# Peripherals.net
KiCad netlist of a schematic drawn in Altium Designer
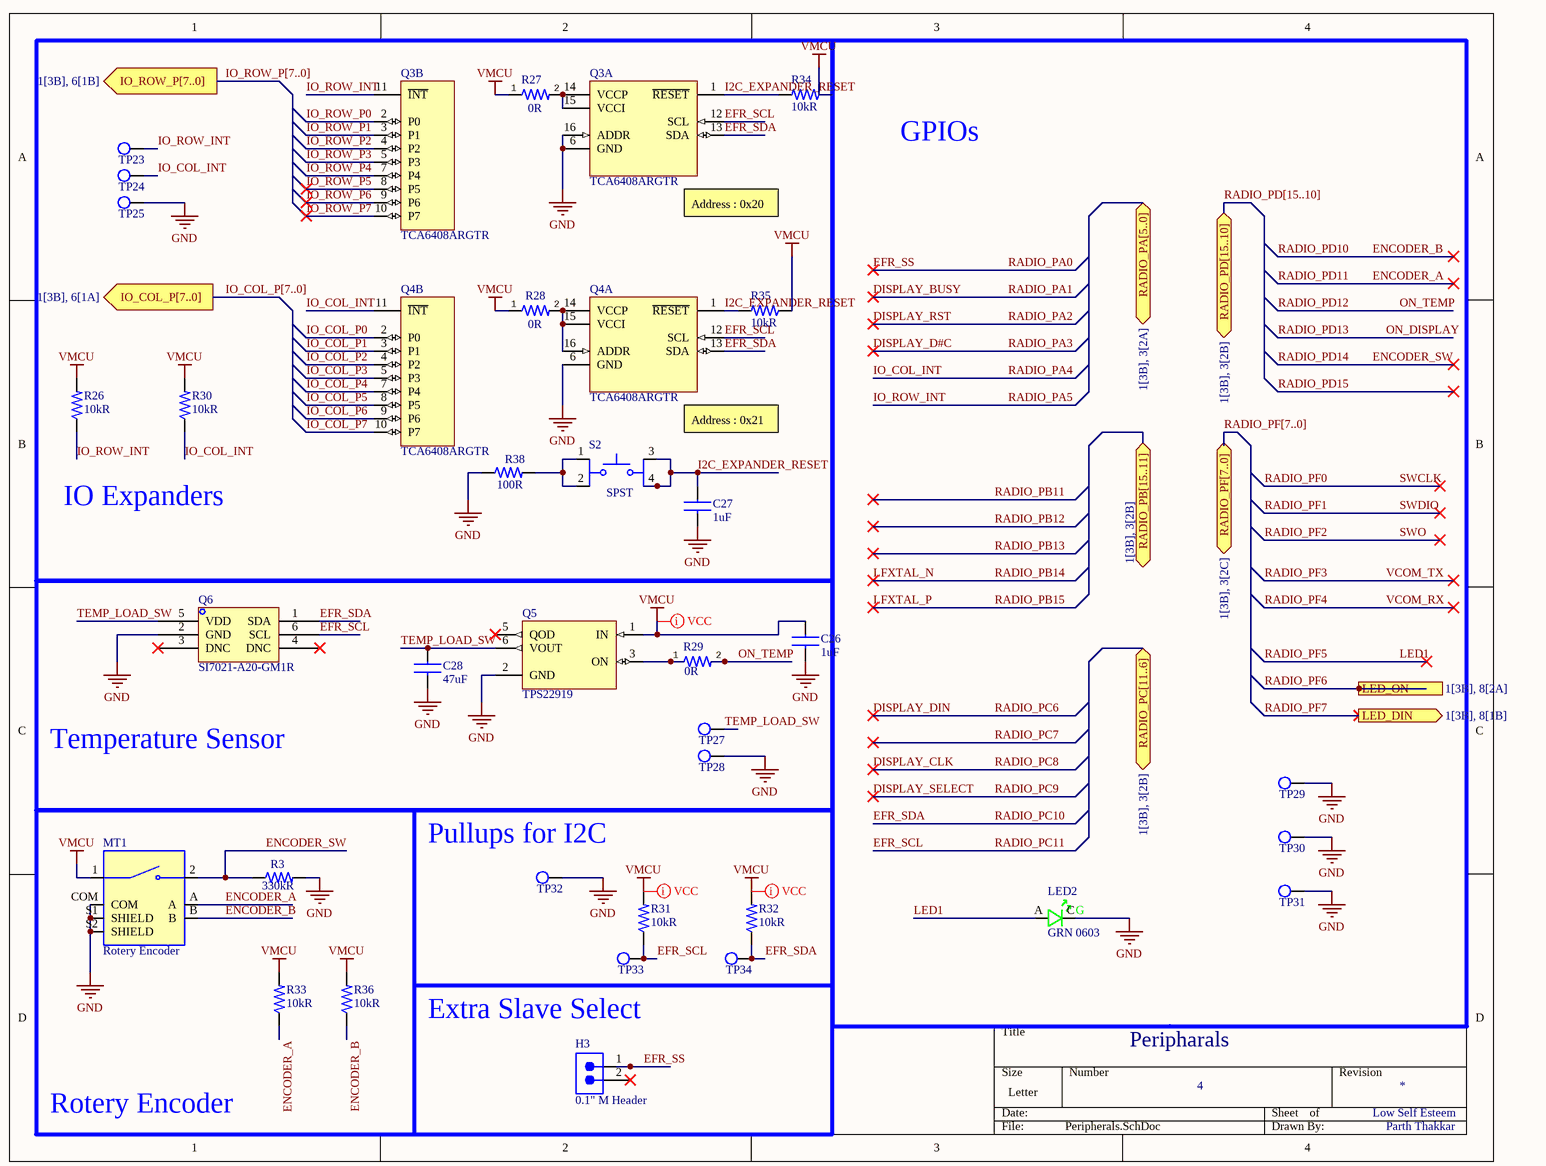
[diagram p0:  Peripherals.SchDoc]

(export (version "E")
  (design (tool "Eeschema 10.0.6"))
  (components
    (comp (ref "C26")
      (value "1uF")
      (footprint "Capacitor 0603")
      (fields
        (field (name "MANUFACTURER") "Murata")
        (field (name "MANUFACTURER PART NUMBER") "GRM188R61A105KA61D")
        (field (name "Comment") "CAP 1uF 10V 0603")
      )
      (libsource (lib "Keyboard_parts") (part "CAP 1uF 10V 0603"))
    )
    (comp (ref "C27")
      (value "1uF")
      (footprint "Capacitor 0603")
      (fields
        (field (name "MANUFACTURER") "Murata")
        (field (name "MANUFACTURER PART NUMBER") "GRM188R61A105KA61D")
        (field (name "Comment") "CAP 1uF 10V 0603")
      )
      (libsource (lib "Keyboard_parts") (part "CAP 1uF 10V 0603"))
    )
    (comp (ref "C28")
      (value "47uF")
      (footprint "CAPACITOR 0805")
      (description "Multilayer Ceramic Capacitors MLCC - SMD/SMT 0805 47uF 10volts *Derate Voltage/Temp")
      (fields
        (field (name "MANUFACTURER") "Murata")
        (field (name "MANUFACTURER PART NUMBER") "GRM21BR61A476ME15K")
      )
      (libsource (lib "Keyboard_parts") (part "CAP 47uF 10V 0805"))
    )
    (comp (ref "H3")
      (value "0.1\" M Header")
      (footprint "2-PIN_MALE_HEADER_01-IN")
      (description "CONN HEADER VERT 2POS 2.54MM")
      (fields
        (field (name "MANUFACTURER") "Sullins")
        (field (name "MANUFACTURER PART NUMBER") "PRPC002SAAN-RC")
      )
      (libsource (lib "InsaneIntegratedLib") (part "PRPC002SAAN-RC"))
    )
    (comp (ref "LED2")
      (value "GRN 0603")
      (footprint "LED 0603")
      (description "LED, 0603, GREEN, 430MCD, 520NM")
      (fields
        (field (name "MANUFACTURER") "Wurth Electronics")
        (field (name "MANUFACTURER PART NUMBER") "150060GS75000")
      )
      (libsource (lib "InsaneIntegratedLib") (part "LED Green 0603"))
    )
    (comp (ref "MT1")
      (value "Rotery Encoder")
      (footprint "Rotery Encoder")
      (description "Rotary Position Encoder, Single, 2 Channels")
      (fields (field (name "MP") "PEC11R-4215F-S0024") (field (name "MANUFACTURER") "Bourns"))
      (libsource (lib "InsaneIntegratedLib") (part "Rotery Encoder"))
    )
    (comp (ref "Q3")
      (value "TCA6408ARGTR")
      (footprint "TCA6408ARGTR - IO Expander")
      (description "Parallel I/O Port, 8-Bit, 8 I/O, CMOS, PQCC16")
      (fields (field (name "MANUFACTURER") "Texas Instruments"))
      (libsource (lib "Keyboard_parts") (part "TCA6408ARGTR"))
    )
    (comp (ref "Q4")
      (value "TCA6408ARGTR")
      (footprint "TCA6408ARGTR - IO Expander")
      (description "Parallel I/O Port, 8-Bit, 8 I/O, CMOS, PQCC16")
      (fields (field (name "MANUFACTURER") "Texas Instruments"))
      (libsource (lib "Keyboard_parts") (part "TCA6408ARGTR"))
    )
    (comp (ref "Q5")
      (value "TPS22919")
      (footprint "TPS22919DCKR - Load SW")
      (description "Buffer/Inverter Based Peripheral Driver, 3A, PDSO6")
      (fields
        (field (name "MANUFACTURER") "Texas Instruments")
        (field (name "MANUFACTURER PART NUMBER") "TPS22919DCKT")
      )
      (libsource (lib "Keyboard_parts") (part "TPS22919"))
    )
    (comp (ref "Q6")
      (value "SI7021-A20-GM1R")
      (footprint "Si7021-A20 - Temp")
      (description "Serial Switch/Digital Sensor, 14 Bit(s), 0.40Cel, Square, Surface Mount")
      (fields (field (name "MANUFACTURER") "Silicon Labs"))
      (libsource (lib "Keyboard_parts") (part "SI7021-A20-GM1R"))
    )
    (comp (ref "R3")
      (value "330kR")
      (footprint "Resistor 0603")
      (fields
        (field (name "MANUFACTURER") "Yageo")
        (field (name "MANUFACTURER PART NUMBER") "RC0603JR-07330KL")
        (field (name "TOLERANCE") "5%")
      )
      (libsource (lib "Keyboard_parts") (part "RES 330K 0603"))
    )
    (comp (ref "R26")
      (value "10kR")
      (footprint "Resistor 0603")
      (fields
        (field (name "MANUFACTURER") "Yageo")
        (field (name "MANUFACTURER PART NUMBER") "RC0603FR-0710KL")
        (field (name "TOLERANCE") "1%")
      )
      (libsource (lib "Keyboard_parts") (part "RES 10K 0603"))
    )
    (comp (ref "R27")
      (value "0R")
      (footprint "Resistor 0402")
      (description "Metal Glaze/thick Film, 0.0625W, 0ohm, Surface Mount, 0402")
      (fields
        (field (name "MANUFACTURER") "Yageo")
        (field (name "MANUFACTURER PART NUMBER") "RC0402JR-070RL")
      )
      (libsource (lib "InsaneIntegratedLib") (part "RES 0R 0402"))
    )
    (comp (ref "R28")
      (value "0R")
      (footprint "Resistor 0402")
      (description "Metal Glaze/thick Film, 0.0625W, 0ohm, Surface Mount, 0402")
      (fields
        (field (name "MANUFACTURER") "Yageo")
        (field (name "MANUFACTURER PART NUMBER") "RC0402JR-070RL")
      )
      (libsource (lib "InsaneIntegratedLib") (part "RES 0R 0402"))
    )
    (comp (ref "R29")
      (value "0R")
      (footprint "Resistor 0402")
      (description "Metal Glaze/thick Film, 0.0625W, 0ohm, Surface Mount, 0402")
      (fields
        (field (name "MANUFACTURER") "Yageo")
        (field (name "MANUFACTURER PART NUMBER") "RC0402JR-070RL")
      )
      (libsource (lib "InsaneIntegratedLib") (part "RES 0R 0402"))
    )
    (comp (ref "R30")
      (value "10kR")
      (footprint "Resistor 0603")
      (fields
        (field (name "MANUFACTURER") "Yageo")
        (field (name "MANUFACTURER PART NUMBER") "RC0603FR-0710KL")
        (field (name "TOLERANCE") "1%")
      )
      (libsource (lib "Keyboard_parts") (part "RES 10K 0603"))
    )
    (comp (ref "R31")
      (value "10kR")
      (footprint "Resistor 0603")
      (fields
        (field (name "MANUFACTURER") "Yageo")
        (field (name "MANUFACTURER PART NUMBER") "RC0603FR-0710KL")
        (field (name "TOLERANCE") "1%")
      )
      (libsource (lib "Keyboard_parts") (part "RES 10K 0603"))
    )
    (comp (ref "R32")
      (value "10kR")
      (footprint "Resistor 0603")
      (fields
        (field (name "MANUFACTURER") "Yageo")
        (field (name "MANUFACTURER PART NUMBER") "RC0603FR-0710KL")
        (field (name "TOLERANCE") "1%")
      )
      (libsource (lib "Keyboard_parts") (part "RES 10K 0603"))
    )
    (comp (ref "R33")
      (value "10kR")
      (footprint "Resistor 0603")
      (fields
        (field (name "MANUFACTURER") "Yageo")
        (field (name "MANUFACTURER PART NUMBER") "RC0603FR-0710KL")
        (field (name "TOLERANCE") "1%")
      )
      (libsource (lib "Keyboard_parts") (part "RES 10K 0603"))
    )
    (comp (ref "R34")
      (value "10kR")
      (footprint "Resistor 0603")
      (fields
        (field (name "MANUFACTURER") "Yageo")
        (field (name "MANUFACTURER PART NUMBER") "RC0603FR-0710KL")
        (field (name "TOLERANCE") "1%")
      )
      (libsource (lib "Keyboard_parts") (part "RES 10K 0603"))
    )
    (comp (ref "R35")
      (value "10kR")
      (footprint "Resistor 0603")
      (fields
        (field (name "MANUFACTURER") "Yageo")
        (field (name "MANUFACTURER PART NUMBER") "RC0603FR-0710KL")
        (field (name "TOLERANCE") "1%")
      )
      (libsource (lib "Keyboard_parts") (part "RES 10K 0603"))
    )
    (comp (ref "R36")
      (value "10kR")
      (footprint "Resistor 0603")
      (fields
        (field (name "MANUFACTURER") "Yageo")
        (field (name "MANUFACTURER PART NUMBER") "RC0603FR-0710KL")
        (field (name "TOLERANCE") "1%")
      )
      (libsource (lib "Keyboard_parts") (part "RES 10K 0603"))
    )
    (comp (ref "R38")
      (value "100R")
      (footprint "Resistor 0603")
      (fields
        (field (name "MANUFACTURER") "Yageo")
        (field (name "MANUFACTURER PART NUMBER") "RC0603FR-07100RL")
        (field (name "TOLERANCE") "1%")
      )
      (libsource (lib "Keyboard_parts") (part "RES 100R 0603"))
    )
    (comp (ref "S2")
      (value "SPST")
      (footprint "SPST")
      (fields
        (field (name "MANUFACTURER") "E-Switch")
        (field (name "MANUFACTURER PART NUMBER") "TL3301NF260QG")
      )
      (libsource (lib "Keyboard_parts") (part "SPST"))
    )
    (comp (ref "TP23")
      (value "Test point")
      (footprint "Test Point")
      (libsource (lib "Keyboard_parts") (part "Test point"))
    )
    (comp (ref "TP24")
      (value "Test point")
      (footprint "Test Point")
      (libsource (lib "Keyboard_parts") (part "Test point"))
    )
    (comp (ref "TP25")
      (value "Test point")
      (footprint "Test Point")
      (libsource (lib "Keyboard_parts") (part "Test point"))
    )
    (comp (ref "TP27")
      (value "Test point")
      (footprint "Test Point")
      (libsource (lib "Keyboard_parts") (part "Test point"))
    )
    (comp (ref "TP28")
      (value "Test point")
      (footprint "Test Point")
      (libsource (lib "Keyboard_parts") (part "Test point"))
    )
    (comp (ref "TP29")
      (value "Test point")
      (footprint "Test Point")
      (libsource (lib "Keyboard_parts") (part "Test point"))
    )
    (comp (ref "TP30")
      (value "Test point")
      (footprint "Test Point")
      (libsource (lib "Keyboard_parts") (part "Test point"))
    )
    (comp (ref "TP31")
      (value "Test point")
      (footprint "Test Point")
      (libsource (lib "Keyboard_parts") (part "Test point"))
    )
    (comp (ref "TP32")
      (value "Test point")
      (footprint "Test Point")
      (libsource (lib "Keyboard_parts") (part "Test point"))
    )
    (comp (ref "TP33")
      (value "Test point")
      (footprint "Test Point")
      (libsource (lib "Keyboard_parts") (part "Test point"))
    )
    (comp (ref "TP34")
      (value "Test point")
      (footprint "Test Point")
      (libsource (lib "Keyboard_parts") (part "Test point"))
    )
  )
  (nets
    (net (code "1") (name "/I2C_EXPANDER_RESET") (class "Default")
      (node (ref "C27") (pin "1") (pinfunction "1_1") (pintype "passive"))
      (node (ref "Q3") (pin "1") (pinfunction "~{RESET}_1") (pintype "passive"))
      (node (ref "Q4") (pin "1") (pinfunction "~{RESET}_1") (pintype "passive"))
      (node (ref "R34") (pin "2") (pinfunction "2_2") (pintype "passive"))
      (node (ref "R35") (pin "2") (pinfunction "2_2") (pintype "passive"))
      (node (ref "S2") (pin "3") (pinfunction "3_3") (pintype "passive"))
      (node (ref "S2") (pin "4") (pinfunction "4_4") (pintype "passive"))
    )
    (net (code "2") (name "/IO_COL_P0") (class "Default")
      (node (ref "Q4") (pin "2") (pinfunction "P0_2") (pintype "bidirectional"))
    )
    (net (code "3") (name "/IO_COL_P1") (class "Default")
      (node (ref "Q4") (pin "3") (pinfunction "P1_3") (pintype "bidirectional"))
    )
    (net (code "4") (name "/IO_COL_P2") (class "Default")
      (node (ref "Q4") (pin "4") (pinfunction "P2_4") (pintype "bidirectional"))
    )
    (net (code "5") (name "/IO_COL_P3") (class "Default")
      (node (ref "Q4") (pin "5") (pinfunction "P3_5") (pintype "bidirectional"))
    )
    (net (code "6") (name "/IO_COL_P4") (class "Default")
      (node (ref "Q4") (pin "7") (pinfunction "P4_7") (pintype "bidirectional"))
    )
    (net (code "7") (name "/IO_COL_P5") (class "Default")
      (node (ref "Q4") (pin "8") (pinfunction "P5_8") (pintype "bidirectional"))
    )
    (net (code "8") (name "/IO_COL_P6") (class "Default")
      (node (ref "Q4") (pin "9") (pinfunction "P6_9") (pintype "bidirectional"))
    )
    (net (code "9") (name "/IO_COL_P7") (class "Default")
      (node (ref "Q4") (pin "10") (pinfunction "P7_10") (pintype "bidirectional"))
    )
    (net (code "11") (name "/IO_ROW_P0") (class "Default")
      (node (ref "Q3") (pin "2") (pinfunction "P0_2") (pintype "bidirectional"))
    )
    (net (code "12") (name "/IO_ROW_P1") (class "Default")
      (node (ref "Q3") (pin "3") (pinfunction "P1_3") (pintype "bidirectional"))
    )
    (net (code "13") (name "/IO_ROW_P2") (class "Default")
      (node (ref "Q3") (pin "4") (pinfunction "P2_4") (pintype "bidirectional"))
    )
    (net (code "14") (name "/IO_ROW_P3") (class "Default")
      (node (ref "Q3") (pin "5") (pinfunction "P3_5") (pintype "bidirectional"))
    )
    (net (code "15") (name "/IO_ROW_P4") (class "Default")
      (node (ref "Q3") (pin "7") (pinfunction "P4_7") (pintype "bidirectional"))
    )
    (net (code "16") (name "/IO_ROW_P5") (class "Default")
      (node (ref "Q3") (pin "8") (pinfunction "P5_8") (pintype "bidirectional+no_connect"))
    )
    (net (code "17") (name "/IO_ROW_P6") (class "Default")
      (node (ref "Q3") (pin "9") (pinfunction "P6_9") (pintype "bidirectional+no_connect"))
    )
    (net (code "18") (name "/IO_ROW_P7") (class "Default")
      (node (ref "Q3") (pin "10") (pinfunction "P7_10") (pintype "bidirectional+no_connect"))
    )
    (net (code "20") (name "/RADIO_PA0") (class "Default")
      (node (ref "H3") (pin "1") (pinfunction "1_1") (pintype "passive"))
    )
    (net (code "24") (name "/RADIO_PA4") (class "Default")
      (node (ref "Q4") (pin "11") (pinfunction "~{INT}_11") (pintype "passive"))
      (node (ref "R30") (pin "1") (pinfunction "1_1") (pintype "passive"))
      (node (ref "TP24") (pin "1") (pinfunction "1_1") (pintype "passive"))
    )
    (net (code "25") (name "/RADIO_PA5") (class "Default")
      (node (ref "Q3") (pin "11") (pinfunction "~{INT}_11") (pintype "passive"))
      (node (ref "R26") (pin "1") (pinfunction "1_1") (pintype "passive"))
      (node (ref "TP23") (pin "1") (pinfunction "1_1") (pintype "passive"))
    )
    (net (code "37") (name "/RADIO_PC10") (class "Default")
      (node (ref "Q3") (pin "13") (pinfunction "SDA_13") (pintype "bidirectional"))
      (node (ref "Q4") (pin "13") (pinfunction "SDA_13") (pintype "bidirectional"))
      (node (ref "Q6") (pin "1") (pinfunction "SDA_1") (pintype "passive"))
      (node (ref "R32") (pin "1") (pinfunction "1_1") (pintype "passive"))
      (node (ref "TP34") (pin "1") (pinfunction "1_1") (pintype "passive"))
    )
    (net (code "38") (name "/RADIO_PC11") (class "Default")
      (node (ref "Q3") (pin "12") (pinfunction "SCL_12") (pintype "input"))
      (node (ref "Q4") (pin "12") (pinfunction "SCL_12") (pintype "input"))
      (node (ref "Q6") (pin "6") (pinfunction "SCL_6") (pintype "passive"))
      (node (ref "R31") (pin "1") (pinfunction "1_1") (pintype "passive"))
      (node (ref "TP33") (pin "1") (pinfunction "1_1") (pintype "passive"))
    )
    (net (code "40") (name "/RADIO_PD10") (class "Default")
      (node (ref "MT1") (pin "B") (pinfunction "B_B") (pintype "passive"))
      (node (ref "R36") (pin "1") (pinfunction "1_1") (pintype "passive"))
    )
    (net (code "41") (name "/RADIO_PD11") (class "Default")
      (node (ref "MT1") (pin "A") (pinfunction "A_A") (pintype "passive"))
      (node (ref "R33") (pin "1") (pinfunction "1_1") (pintype "passive"))
    )
    (net (code "42") (name "/RADIO_PD12") (class "Default")
      (node (ref "R29") (pin "2") (pinfunction "2_2") (pintype "passive"))
    )
    (net (code "44") (name "/RADIO_PD14") (class "Default")
      (node (ref "MT1") (pin "2") (pinfunction "2_2") (pintype "passive"))
      (node (ref "R3") (pin "1") (pinfunction "1_1") (pintype "passive"))
    )
    (net (code "52") (name "/RADIO_PF5") (class "Default")
      (node (ref "LED2") (pin "A") (pinfunction "A_A") (pintype "passive"))
    )
    (net (code "56") (name "/TEMP_LOAD_SW") (class "Default")
      (node (ref "C28") (pin "1") (pinfunction "1_1") (pintype "passive"))
      (node (ref "Q5") (pin "6") (pinfunction "VOUT_6") (pintype "output"))
      (node (ref "Q6") (pin "5") (pinfunction "VDD_5") (pintype "passive"))
      (node (ref "TP27") (pin "1") (pinfunction "1_1") (pintype "passive"))
    )
    (net (code "57") (name "GND") (class "Default")
      (node (ref "C26") (pin "2") (pinfunction "2_2") (pintype "passive"))
      (node (ref "C27") (pin "2") (pinfunction "2_2") (pintype "passive"))
      (node (ref "C28") (pin "2") (pinfunction "2_2") (pintype "passive"))
      (node (ref "LED2") (pin "C") (pinfunction "C_C") (pintype "passive"))
      (node (ref "MT1") (pin "COM") (pinfunction "COM_COM") (pintype "passive"))
      (node (ref "MT1") (pin "S1") (pinfunction "SHIELD_S1") (pintype "passive"))
      (node (ref "MT1") (pin "S2") (pinfunction "SHIELD_S2") (pintype "passive"))
      (node (ref "Q3") (pin "16") (pinfunction "ADDR_16") (pintype "input"))
      (node (ref "Q3") (pin "6") (pinfunction "GND_6") (pintype "passive"))
      (node (ref "Q4") (pin "6") (pinfunction "GND_6") (pintype "passive"))
      (node (ref "Q5") (pin "2") (pinfunction "GND_2") (pintype "passive"))
      (node (ref "Q6") (pin "2") (pinfunction "GND_2") (pintype "passive"))
      (node (ref "R3") (pin "2") (pinfunction "2_2") (pintype "passive"))
      (node (ref "R38") (pin "1") (pinfunction "1_1") (pintype "passive"))
      (node (ref "TP25") (pin "1") (pinfunction "1_1") (pintype "passive"))
      (node (ref "TP28") (pin "1") (pinfunction "1_1") (pintype "passive"))
      (node (ref "TP29") (pin "1") (pinfunction "1_1") (pintype "passive"))
      (node (ref "TP30") (pin "1") (pinfunction "1_1") (pintype "passive"))
      (node (ref "TP31") (pin "1") (pinfunction "1_1") (pintype "passive"))
      (node (ref "TP32") (pin "1") (pinfunction "1_1") (pintype "passive"))
    )
    (net (code "58") (name "Net-(Q3A-VCCI)") (class "Default")
      (node (ref "Q3") (pin "14") (pinfunction "VCCP_14") (pintype "power_in"))
      (node (ref "Q3") (pin "15") (pinfunction "VCCI_15") (pintype "power_in"))
      (node (ref "R27") (pin "2") (pinfunction "2_2") (pintype "passive"))
    )
    (net (code "59") (name "Net-(Q4A-ADDR)") (class "Default")
      (node (ref "Q4") (pin "14") (pinfunction "VCCP_14") (pintype "power_in"))
      (node (ref "Q4") (pin "15") (pinfunction "VCCI_15") (pintype "power_in"))
      (node (ref "Q4") (pin "16") (pinfunction "ADDR_16") (pintype "input"))
      (node (ref "R28") (pin "2") (pinfunction "2_2") (pintype "passive"))
    )
    (net (code "60") (name "Net-(Q5-ON)") (class "Default")
      (node (ref "Q5") (pin "3") (pinfunction "ON_3") (pintype "bidirectional"))
      (node (ref "R29") (pin "1") (pinfunction "1_1") (pintype "passive"))
    )
    (net (code "61") (name "Net-(R38-Pad2)") (class "Default")
      (node (ref "R38") (pin "2") (pinfunction "2_2") (pintype "passive"))
      (node (ref "S2") (pin "1") (pinfunction "1_1") (pintype "passive"))
      (node (ref "S2") (pin "2") (pinfunction "2_2") (pintype "passive"))
    )
    (net (code "62") (name "VMCU") (class "Default")
      (node (ref "C26") (pin "1") (pinfunction "1_1") (pintype "passive"))
      (node (ref "MT1") (pin "1") (pinfunction "1_1") (pintype "passive"))
      (node (ref "Q5") (pin "1") (pinfunction "IN_1") (pintype "input"))
      (node (ref "R26") (pin "2") (pinfunction "2_2") (pintype "passive"))
      (node (ref "R27") (pin "1") (pinfunction "1_1") (pintype "passive"))
      (node (ref "R28") (pin "1") (pinfunction "1_1") (pintype "passive"))
      (node (ref "R30") (pin "2") (pinfunction "2_2") (pintype "passive"))
      (node (ref "R31") (pin "2") (pinfunction "2_2") (pintype "passive"))
      (node (ref "R32") (pin "2") (pinfunction "2_2") (pintype "passive"))
      (node (ref "R33") (pin "2") (pinfunction "2_2") (pintype "passive"))
      (node (ref "R34") (pin "1") (pinfunction "1_1") (pintype "passive"))
      (node (ref "R35") (pin "1") (pinfunction "1_1") (pintype "passive"))
      (node (ref "R36") (pin "2") (pinfunction "2_2") (pintype "passive"))
    )
    (net (code "63") (name "unconnected-(H3-Pad2)") (class "Default")
      (node (ref "H3") (pin "2") (pinfunction "2_2") (pintype "passive+no_connect"))
    )
    (net (code "64") (name "unconnected-(Q5-QOD-Pad5)") (class "Default")
      (node (ref "Q5") (pin "5") (pinfunction "QOD_5") (pintype "output+no_connect"))
    )
    (net (code "65") (name "unconnected-(Q6-DNC-Pad3)") (class "Default")
      (node (ref "Q6") (pin "3") (pinfunction "DNC_3") (pintype "passive+no_connect"))
    )
    (net (code "66") (name "unconnected-(Q6-DNC-Pad4)") (class "Default")
      (node (ref "Q6") (pin "4") (pinfunction "DNC_4") (pintype "passive+no_connect"))
    )
  )
)
